# Soldering_Iron_Controls_v0_4.net
KiCad netlist of a schematic drawn in EAGLE
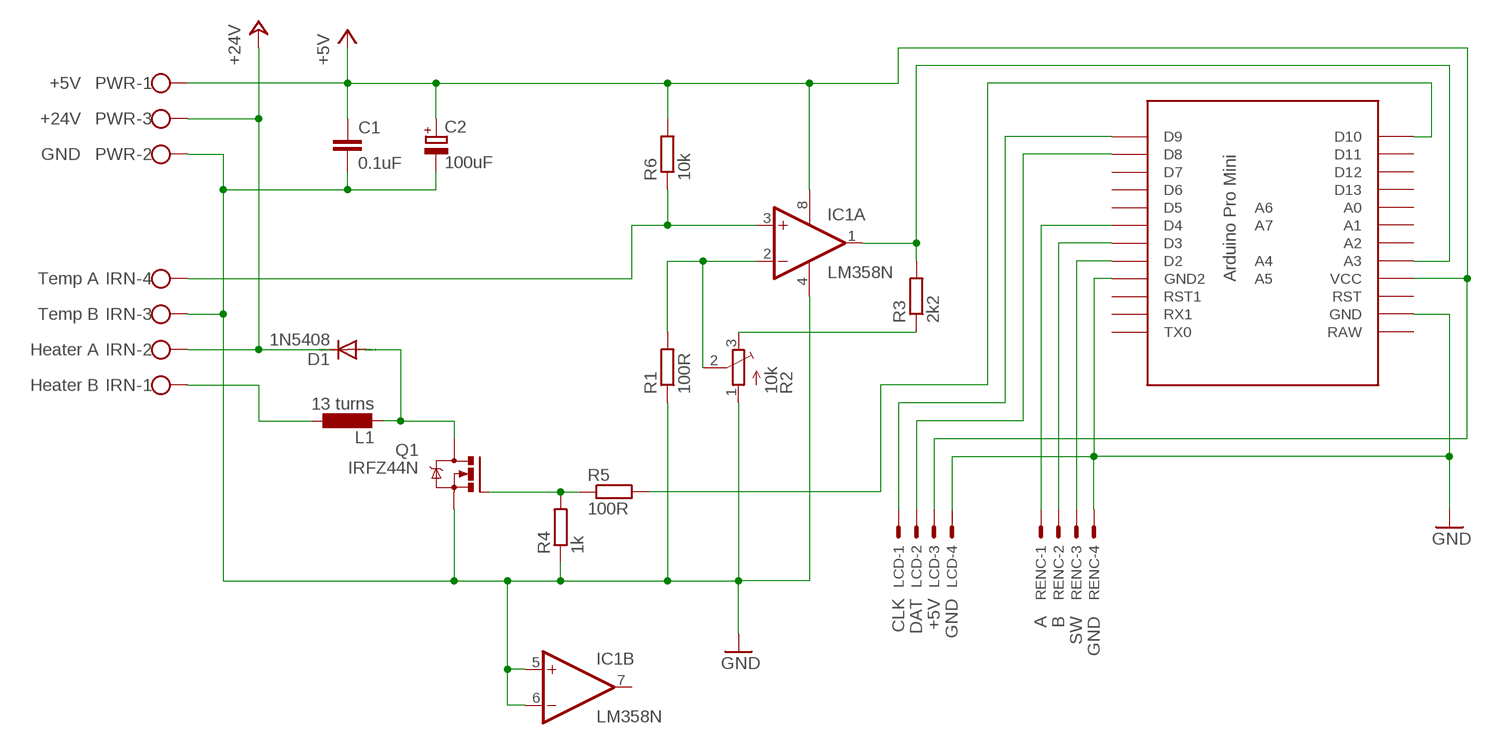
[diagram p0: schematic, sheet 1]

(export (version "E")
  (design (tool "Eeschema 10.0.6"))
  (components
    (comp (ref "C1")
      (value "0.1uF")
      (footprint "eagle-import:C025-024X044")
      (libsource (lib "eagle-import") (part "C-EU025-024X044"))
    )
    (comp (ref "C2")
      (value "100uF")
      (footprint "eagle-import:E5-6")
      (libsource (lib "eagle-import") (part "CPOL-EUE5-6"))
    )
    (comp (ref "D1")
      (value "1N5408")
      (footprint "eagle-import:DO27-15")
      (libsource (lib "eagle-import") (part "DIODE-DO27-15"))
    )
    (comp (ref "IC1")
      (value "LM358N")
      (footprint "eagle-import:DIL08")
      (libsource (lib "eagle-import") (part "LM358N"))
    )
    (comp (ref "IRN")
      (value "W237-4")
      (footprint "eagle-import:W237-4")
      (libsource (lib "eagle-import") (part "W237-4"))
    )
    (comp (ref "L1")
      (value "13 turns")
      (footprint "eagle-import:TJ3-U1")
      (libsource (lib "eagle-import") (part "L-EUTJ3-U1"))
    )
    (comp (ref "LCD")
      (value "22-05-7048-04")
      (footprint "eagle-import:7395-04")
      (libsource (lib "eagle-import") (part "22-?-0405-7048"))
    )
    (comp (ref "PWR")
      (value "W237-103")
      (footprint "eagle-import:W237-103")
      (fields (field (name "MPN") "237-103"))
      (libsource (lib "eagle-import") (part "W237-103"))
    )
    (comp (ref "Q1")
      (value "IRFZ44N")
      (footprint "eagle-import:TO220BV")
      (libsource (lib "eagle-import") (part "IRFZ44N"))
    )
    (comp (ref "R1")
      (value "100R")
      (footprint "eagle-import:0207_7@1")
      (libsource (lib "eagle-import") (part "R-EU_0207/7"))
    )
    (comp (ref "R2")
      (value "10k")
      (footprint "eagle-import:RM-065")
      (libsource (lib "eagle-import") (part "TRIM_EU-RM-065"))
    )
    (comp (ref "R3")
      (value "2k2")
      (footprint "eagle-import:0207_7@1")
      (libsource (lib "eagle-import") (part "R-EU_0207/7"))
    )
    (comp (ref "R4")
      (value "1k")
      (footprint "eagle-import:0207_7@1")
      (libsource (lib "eagle-import") (part "R-EU_0207/7"))
    )
    (comp (ref "R5")
      (value "100R")
      (footprint "eagle-import:0207_7@1")
      (libsource (lib "eagle-import") (part "R-EU_0207/7"))
    )
    (comp (ref "R6")
      (value "10k")
      (footprint "eagle-import:0207_7@1")
      (libsource (lib "eagle-import") (part "R-EU_0207/7"))
    )
    (comp (ref "RENC")
      (value "22-05-7048-04")
      (footprint "eagle-import:7395-04")
      (libsource (lib "eagle-import") (part "22-?-0405-7048"))
    )
    (comp (ref "U$1")
      (value "PRO-MINI-2X")
      (footprint "eagle-import:PRO-MINI-2X")
      (libsource (lib "eagle-import") (part "PRO-MINI-2X"))
    )
  )
  (nets
    (net (code "1") (name "+5V") (class "Default")
      (node (ref "C1") (pin "1") (pinfunction "1_1") (pintype "passive"))
      (node (ref "C2") (pin "+") (pinfunction "+_+") (pintype "passive"))
      (node (ref "IC1") (pin "8") (pinfunction "V+_8") (pintype "power_in"))
      (node (ref "LCD") (pin "3") (pinfunction "S_3") (pintype "passive"))
      (node (ref "PWR") (pin "1") (pinfunction "KL_1") (pintype "passive"))
      (node (ref "R6") (pin "2") (pinfunction "2_2") (pintype "passive"))
      (node (ref "U$1") (pin "VCC") (pinfunction "VCC_VCC") (pintype "bidirectional"))
    )
    (net (code "2") (name "+24V") (class "Default")
      (node (ref "D1") (pin "C") (pinfunction "C_C") (pintype "passive"))
      (node (ref "IRN") (pin "2") (pinfunction "KL_2") (pintype "passive"))
      (node (ref "PWR") (pin "3") (pinfunction "KL_3") (pintype "passive"))
    )
    (net (code "3") (name "GND") (class "Default")
      (node (ref "C1") (pin "2") (pinfunction "2_2") (pintype "passive"))
      (node (ref "C2") (pin "-") (pinfunction "-_-") (pintype "passive"))
      (node (ref "IC1") (pin "4") (pinfunction "V-_4") (pintype "power_in"))
      (node (ref "IC1") (pin "5") (pinfunction "+IN_5") (pintype "input"))
      (node (ref "IC1") (pin "6") (pinfunction "-IN_6") (pintype "input"))
      (node (ref "IRN") (pin "3") (pinfunction "KL_3") (pintype "passive"))
      (node (ref "LCD") (pin "4") (pinfunction "S_4") (pintype "passive"))
      (node (ref "PWR") (pin "2") (pinfunction "KL_2") (pintype "passive"))
      (node (ref "Q1") (pin "S") (pinfunction "S_S") (pintype "passive"))
      (node (ref "R1") (pin "1") (pinfunction "1_1") (pintype "passive"))
      (node (ref "R2") (pin "1") (pinfunction "A_1") (pintype "passive"))
      (node (ref "R4") (pin "1") (pinfunction "1_1") (pintype "passive"))
      (node (ref "RENC") (pin "4") (pinfunction "S_4") (pintype "passive"))
      (node (ref "U$1") (pin "GND") (pinfunction "GND_GND") (pintype "bidirectional"))
      (node (ref "U$1") (pin "GND1") (pinfunction "GND2_GND1") (pintype "bidirectional"))
    )
    (net (code "4") (name "Net-(D1-PadA)") (class "Default")
      (node (ref "D1") (pin "A") (pinfunction "A_A") (pintype "passive"))
      (node (ref "L1") (pin "2") (pinfunction "2_2") (pintype "passive"))
      (node (ref "Q1") (pin "D") (pinfunction "D_D") (pintype "passive"))
    )
    (net (code "5") (name "Net-(IC1A-+IN)") (class "Default")
      (node (ref "IC1") (pin "3") (pinfunction "+IN_3") (pintype "input"))
      (node (ref "IRN") (pin "4") (pinfunction "KL_4") (pintype "passive"))
      (node (ref "R6") (pin "1") (pinfunction "1_1") (pintype "passive"))
    )
    (net (code "6") (name "Net-(IC1A--IN)") (class "Default")
      (node (ref "IC1") (pin "2") (pinfunction "-IN_2") (pintype "input"))
      (node (ref "R1") (pin "2") (pinfunction "2_2") (pintype "passive"))
      (node (ref "R2") (pin "2") (pinfunction "S_2") (pintype "passive"))
    )
    (net (code "7") (name "Net-(IC1A-OUT)") (class "Default")
      (node (ref "IC1") (pin "1") (pinfunction "OUT_1") (pintype "output"))
      (node (ref "R3") (pin "2") (pinfunction "2_2") (pintype "passive"))
      (node (ref "U$1") (pin "A3") (pinfunction "A3_A3") (pintype "bidirectional"))
    )
    (net (code "8") (name "Net-(IRNA-KL)") (class "Default")
      (node (ref "IRN") (pin "1") (pinfunction "KL_1") (pintype "passive"))
      (node (ref "L1") (pin "1") (pinfunction "1_1") (pintype "passive"))
    )
    (net (code "9") (name "Net-(LCDA-S)") (class "Default")
      (node (ref "LCD") (pin "1") (pinfunction "S_1") (pintype "passive"))
      (node (ref "U$1") (pin "D9") (pinfunction "D9_D9") (pintype "bidirectional"))
    )
    (net (code "10") (name "Net-(LCDB-S)") (class "Default")
      (node (ref "LCD") (pin "2") (pinfunction "S_2") (pintype "passive"))
      (node (ref "U$1") (pin "D8") (pinfunction "D8_D8") (pintype "bidirectional"))
    )
    (net (code "11") (name "Net-(Q1-PadG)") (class "Default")
      (node (ref "Q1") (pin "G") (pinfunction "G_G") (pintype "passive"))
      (node (ref "R4") (pin "2") (pinfunction "2_2") (pintype "passive"))
      (node (ref "R5") (pin "1") (pinfunction "1_1") (pintype "passive"))
    )
    (net (code "12") (name "Net-(R2-E)") (class "Default")
      (node (ref "R2") (pin "3") (pinfunction "E_3") (pintype "passive"))
      (node (ref "R3") (pin "1") (pinfunction "1_1") (pintype "passive"))
    )
    (net (code "13") (name "Net-(R5-Pad2)") (class "Default")
      (node (ref "R5") (pin "2") (pinfunction "2_2") (pintype "passive"))
      (node (ref "U$1") (pin "D10") (pinfunction "D10_D10") (pintype "bidirectional"))
    )
    (net (code "14") (name "Net-(RENCA-S)") (class "Default")
      (node (ref "RENC") (pin "1") (pinfunction "S_1") (pintype "passive"))
      (node (ref "U$1") (pin "D4") (pinfunction "D4_D4") (pintype "bidirectional"))
    )
    (net (code "15") (name "Net-(RENCB-S)") (class "Default")
      (node (ref "RENC") (pin "2") (pinfunction "S_2") (pintype "passive"))
      (node (ref "U$1") (pin "D3") (pinfunction "D3_D3") (pintype "bidirectional"))
    )
    (net (code "16") (name "Net-(RENCC-S)") (class "Default")
      (node (ref "RENC") (pin "3") (pinfunction "S_3") (pintype "passive"))
      (node (ref "U$1") (pin "D2") (pinfunction "D2_D2") (pintype "bidirectional"))
    )
    (net (code "17") (name "unconnected-(IC1B-OUT-Pad7)") (class "Default")
      (node (ref "IC1") (pin "7") (pinfunction "OUT_7") (pintype "output"))
    )
    (net (code "18") (name "unconnected-(U$1-PadA0)") (class "Default")
      (node (ref "U$1") (pin "A0") (pinfunction "A0_A0") (pintype "bidirectional"))
    )
    (net (code "19") (name "unconnected-(U$1-PadA1)") (class "Default")
      (node (ref "U$1") (pin "A1") (pinfunction "A1_A1") (pintype "bidirectional"))
    )
    (net (code "20") (name "unconnected-(U$1-PadA2)") (class "Default")
      (node (ref "U$1") (pin "A2") (pinfunction "A2_A2") (pintype "bidirectional"))
    )
    (net (code "21") (name "unconnected-(U$1-PadA4)") (class "Default")
      (node (ref "U$1") (pin "A4") (pinfunction "A4_A4") (pintype "bidirectional"))
    )
    (net (code "22") (name "unconnected-(U$1-PadA5)") (class "Default")
      (node (ref "U$1") (pin "A5") (pinfunction "A5_A5") (pintype "bidirectional"))
    )
    (net (code "23") (name "unconnected-(U$1-PadA6)") (class "Default")
      (node (ref "U$1") (pin "A6") (pinfunction "A6_A6") (pintype "bidirectional"))
    )
    (net (code "24") (name "unconnected-(U$1-PadA7)") (class "Default")
      (node (ref "U$1") (pin "A7") (pinfunction "A7_A7") (pintype "bidirectional"))
    )
    (net (code "25") (name "unconnected-(U$1-PadD5)") (class "Default")
      (node (ref "U$1") (pin "D5") (pinfunction "D5_D5") (pintype "bidirectional"))
    )
    (net (code "26") (name "unconnected-(U$1-PadD6)") (class "Default")
      (node (ref "U$1") (pin "D6") (pinfunction "D6_D6") (pintype "bidirectional"))
    )
    (net (code "27") (name "unconnected-(U$1-PadD7)") (class "Default")
      (node (ref "U$1") (pin "D7") (pinfunction "D7_D7") (pintype "bidirectional"))
    )
    (net (code "28") (name "unconnected-(U$1-PadD11)") (class "Default")
      (node (ref "U$1") (pin "D11") (pinfunction "D11_D11") (pintype "bidirectional"))
    )
    (net (code "29") (name "unconnected-(U$1-PadD12)") (class "Default")
      (node (ref "U$1") (pin "D12") (pinfunction "D12_D12") (pintype "bidirectional"))
    )
    (net (code "30") (name "unconnected-(U$1-PadD13)") (class "Default")
      (node (ref "U$1") (pin "D13") (pinfunction "D13_D13") (pintype "bidirectional"))
    )
    (net (code "31") (name "unconnected-(U$1-PadRAW)") (class "Default")
      (node (ref "U$1") (pin "RAW") (pinfunction "RAW_RAW") (pintype "bidirectional"))
    )
    (net (code "32") (name "unconnected-(U$1-PadRST)") (class "Default")
      (node (ref "U$1") (pin "RST") (pinfunction "RST_RST") (pintype "bidirectional"))
    )
    (net (code "33") (name "unconnected-(U$1-PadRST1)") (class "Default")
      (node (ref "U$1") (pin "RST1") (pinfunction "RST1_RST1") (pintype "bidirectional"))
    )
    (net (code "34") (name "unconnected-(U$1-PadRX1)") (class "Default")
      (node (ref "U$1") (pin "RX1") (pinfunction "RX1_RX1") (pintype "bidirectional"))
    )
    (net (code "35") (name "unconnected-(U$1-PadTX0)") (class "Default")
      (node (ref "U$1") (pin "TX0") (pinfunction "TX0_TX0") (pintype "bidirectional"))
    )
  )
)
